# MB1134.net
KiCad netlist of a schematic drawn in Altium Designer
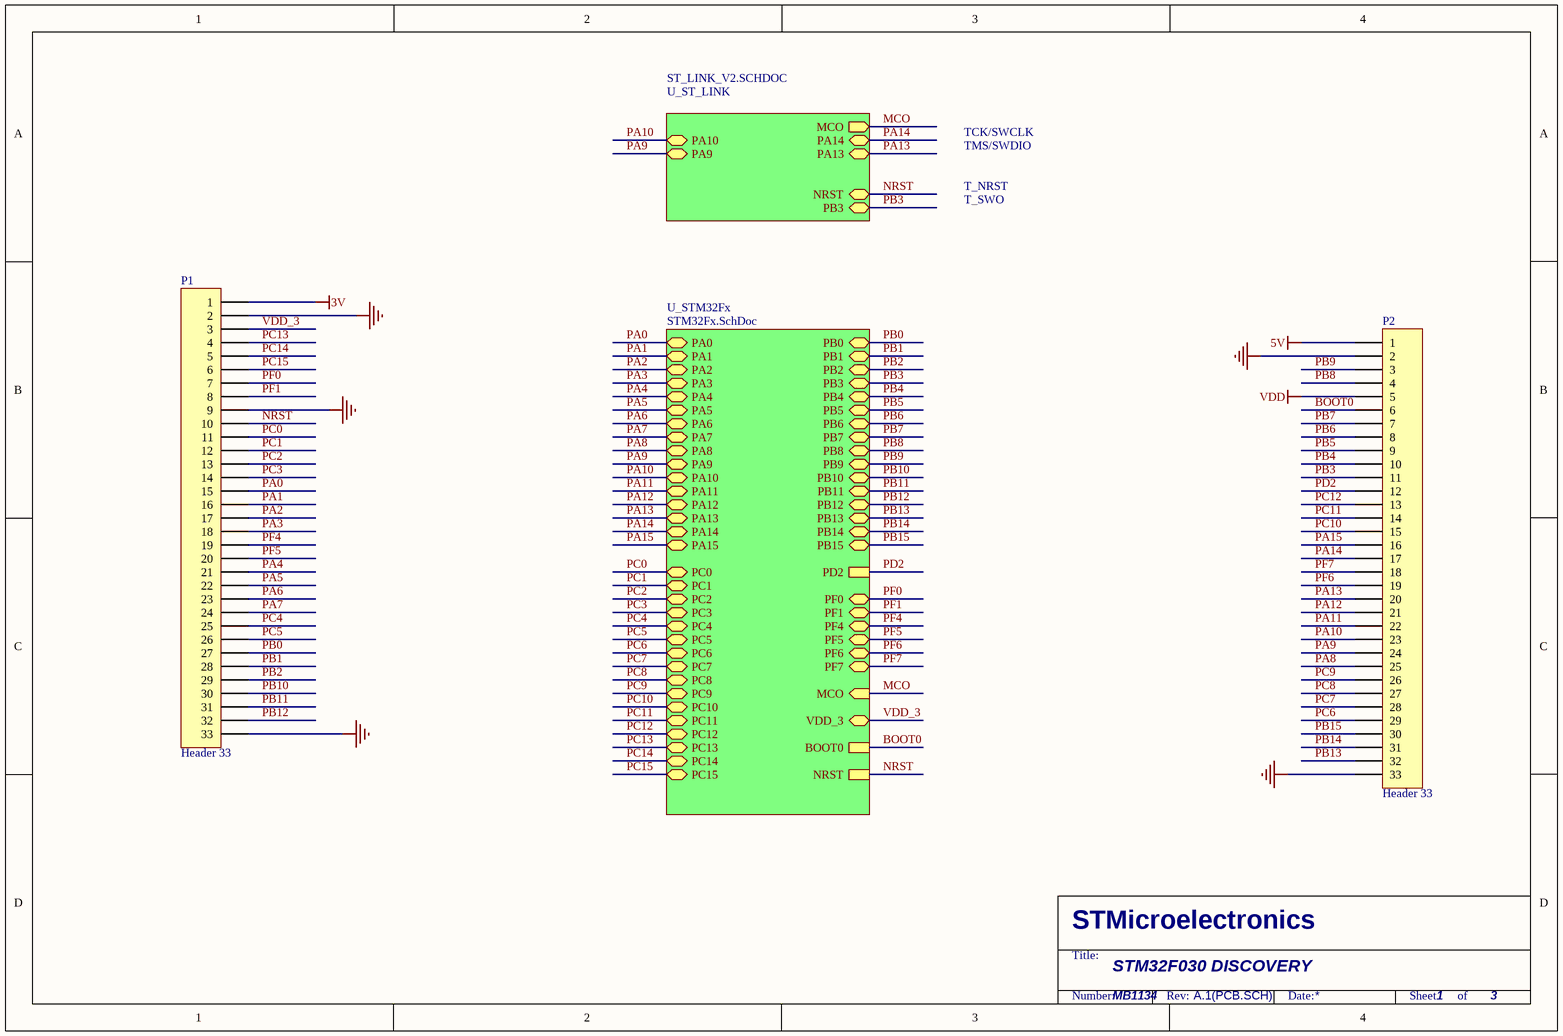
[diagram p0: MB1134.SchDoc]

(export (version "E")
  (design (tool "Eeschema 10.0.6"))
  (components
    (comp (ref "P1")
      (value "Header 33")
      (footprint "HDR1X33")
      (description "Header, 33-Pin")
      (fields (field (name "PUBLISHER") "Altium Limited"))
      (libsource (lib "") (part "Header 33_1"))
    )
    (comp (ref "P2")
      (value "Header 33")
      (footprint "HDR1X33")
      (description "Header, 33-Pin")
      (fields (field (name "PUBLISHER") "Altium Limited"))
      (libsource (lib "MB1034") (part "Header 33"))
    )
  )
  (nets
    (net (code "1") (name "/BOOT0") (class "Default")
      (node (ref "P2") (pin "6") (pinfunction "6_6") (pintype "passive"))
    )
    (net (code "3") (name "/NRST") (class "Default")
      (node (ref "P1") (pin "10") (pinfunction "10_10") (pintype "passive"))
    )
    (net (code "4") (name "/PA0") (class "Default")
      (node (ref "P1") (pin "15") (pinfunction "15_15") (pintype "passive"))
    )
    (net (code "5") (name "/PA1") (class "Default")
      (node (ref "P1") (pin "16") (pinfunction "16_16") (pintype "passive"))
    )
    (net (code "6") (name "/PA2") (class "Default")
      (node (ref "P1") (pin "17") (pinfunction "17_17") (pintype "passive"))
    )
    (net (code "7") (name "/PA3") (class "Default")
      (node (ref "P1") (pin "18") (pinfunction "18_18") (pintype "passive"))
    )
    (net (code "8") (name "/PA4") (class "Default")
      (node (ref "P1") (pin "21") (pinfunction "21_21") (pintype "passive"))
    )
    (net (code "9") (name "/PA5") (class "Default")
      (node (ref "P1") (pin "22") (pinfunction "22_22") (pintype "passive"))
    )
    (net (code "10") (name "/PA6") (class "Default")
      (node (ref "P1") (pin "23") (pinfunction "23_23") (pintype "passive"))
    )
    (net (code "11") (name "/PA7") (class "Default")
      (node (ref "P1") (pin "24") (pinfunction "24_24") (pintype "passive"))
    )
    (net (code "12") (name "/PA8") (class "Default")
      (node (ref "P2") (pin "25") (pinfunction "25_25") (pintype "passive"))
    )
    (net (code "13") (name "/PA9") (class "Default")
      (node (ref "P2") (pin "24") (pinfunction "24_24") (pintype "passive"))
    )
    (net (code "14") (name "/PA10") (class "Default")
      (node (ref "P2") (pin "23") (pinfunction "23_23") (pintype "passive"))
    )
    (net (code "15") (name "/PA11") (class "Default")
      (node (ref "P2") (pin "22") (pinfunction "22_22") (pintype "passive"))
    )
    (net (code "16") (name "/PA12") (class "Default")
      (node (ref "P2") (pin "21") (pinfunction "21_21") (pintype "passive"))
    )
    (net (code "17") (name "/PA13") (class "Default")
      (node (ref "P2") (pin "20") (pinfunction "20_20") (pintype "passive"))
    )
    (net (code "18") (name "/PA14") (class "Default")
      (node (ref "P2") (pin "17") (pinfunction "17_17") (pintype "passive"))
    )
    (net (code "19") (name "/PA15") (class "Default")
      (node (ref "P2") (pin "16") (pinfunction "16_16") (pintype "passive"))
    )
    (net (code "20") (name "/PB0") (class "Default")
      (node (ref "P1") (pin "27") (pinfunction "27_27") (pintype "passive"))
    )
    (net (code "21") (name "/PB1") (class "Default")
      (node (ref "P1") (pin "28") (pinfunction "28_28") (pintype "passive"))
    )
    (net (code "22") (name "/PB2") (class "Default")
      (node (ref "P1") (pin "29") (pinfunction "29_29") (pintype "passive"))
    )
    (net (code "23") (name "/PB3") (class "Default")
      (node (ref "P2") (pin "11") (pinfunction "11_11") (pintype "passive"))
    )
    (net (code "24") (name "/PB4") (class "Default")
      (node (ref "P2") (pin "10") (pinfunction "10_10") (pintype "passive"))
    )
    (net (code "25") (name "/PB5") (class "Default")
      (node (ref "P2") (pin "9") (pinfunction "9_9") (pintype "passive"))
    )
    (net (code "26") (name "/PB6") (class "Default")
      (node (ref "P2") (pin "8") (pinfunction "8_8") (pintype "passive"))
    )
    (net (code "27") (name "/PB7") (class "Default")
      (node (ref "P2") (pin "7") (pinfunction "7_7") (pintype "passive"))
    )
    (net (code "28") (name "/PB8") (class "Default")
      (node (ref "P2") (pin "4") (pinfunction "4_4") (pintype "passive"))
    )
    (net (code "29") (name "/PB9") (class "Default")
      (node (ref "P2") (pin "3") (pinfunction "3_3") (pintype "passive"))
    )
    (net (code "30") (name "/PB10") (class "Default")
      (node (ref "P1") (pin "30") (pinfunction "30_30") (pintype "passive"))
    )
    (net (code "31") (name "/PB11") (class "Default")
      (node (ref "P1") (pin "31") (pinfunction "31_31") (pintype "passive"))
    )
    (net (code "32") (name "/PB12") (class "Default")
      (node (ref "P1") (pin "32") (pinfunction "32_32") (pintype "passive"))
    )
    (net (code "33") (name "/PB13") (class "Default")
      (node (ref "P2") (pin "32") (pinfunction "32_32") (pintype "passive"))
    )
    (net (code "34") (name "/PB14") (class "Default")
      (node (ref "P2") (pin "31") (pinfunction "31_31") (pintype "passive"))
    )
    (net (code "35") (name "/PB15") (class "Default")
      (node (ref "P2") (pin "30") (pinfunction "30_30") (pintype "passive"))
    )
    (net (code "36") (name "/PC0") (class "Default")
      (node (ref "P1") (pin "11") (pinfunction "11_11") (pintype "passive"))
    )
    (net (code "37") (name "/PC1") (class "Default")
      (node (ref "P1") (pin "12") (pinfunction "12_12") (pintype "passive"))
    )
    (net (code "38") (name "/PC2") (class "Default")
      (node (ref "P1") (pin "13") (pinfunction "13_13") (pintype "passive"))
    )
    (net (code "39") (name "/PC3") (class "Default")
      (node (ref "P1") (pin "14") (pinfunction "14_14") (pintype "passive"))
    )
    (net (code "40") (name "/PC4") (class "Default")
      (node (ref "P1") (pin "25") (pinfunction "25_25") (pintype "passive"))
    )
    (net (code "41") (name "/PC5") (class "Default")
      (node (ref "P1") (pin "26") (pinfunction "26_26") (pintype "passive"))
    )
    (net (code "42") (name "/PC6") (class "Default")
      (node (ref "P2") (pin "29") (pinfunction "29_29") (pintype "passive"))
    )
    (net (code "43") (name "/PC7") (class "Default")
      (node (ref "P2") (pin "28") (pinfunction "28_28") (pintype "passive"))
    )
    (net (code "44") (name "/PC8") (class "Default")
      (node (ref "P2") (pin "27") (pinfunction "27_27") (pintype "passive"))
    )
    (net (code "45") (name "/PC9") (class "Default")
      (node (ref "P2") (pin "26") (pinfunction "26_26") (pintype "passive"))
    )
    (net (code "46") (name "/PC10") (class "Default")
      (node (ref "P2") (pin "15") (pinfunction "15_15") (pintype "passive"))
    )
    (net (code "47") (name "/PC11") (class "Default")
      (node (ref "P2") (pin "14") (pinfunction "14_14") (pintype "passive"))
    )
    (net (code "48") (name "/PC12") (class "Default")
      (node (ref "P2") (pin "13") (pinfunction "13_13") (pintype "passive"))
    )
    (net (code "49") (name "/PC13") (class "Default")
      (node (ref "P1") (pin "4") (pinfunction "4_4") (pintype "passive"))
    )
    (net (code "50") (name "/PC14") (class "Default")
      (node (ref "P1") (pin "5") (pinfunction "5_5") (pintype "passive"))
    )
    (net (code "51") (name "/PC15") (class "Default")
      (node (ref "P1") (pin "6") (pinfunction "6_6") (pintype "passive"))
    )
    (net (code "52") (name "/PD2") (class "Default")
      (node (ref "P2") (pin "12") (pinfunction "12_12") (pintype "passive"))
    )
    (net (code "53") (name "/PF0") (class "Default")
      (node (ref "P1") (pin "7") (pinfunction "7_7") (pintype "passive"))
    )
    (net (code "54") (name "/PF1") (class "Default")
      (node (ref "P1") (pin "8") (pinfunction "8_8") (pintype "passive"))
    )
    (net (code "55") (name "/PF4") (class "Default")
      (node (ref "P1") (pin "19") (pinfunction "19_19") (pintype "passive"))
    )
    (net (code "56") (name "/PF5") (class "Default")
      (node (ref "P1") (pin "20") (pinfunction "20_20") (pintype "passive"))
    )
    (net (code "57") (name "/PF6") (class "Default")
      (node (ref "P2") (pin "19") (pinfunction "19_19") (pintype "passive"))
    )
    (net (code "58") (name "/PF7") (class "Default")
      (node (ref "P2") (pin "18") (pinfunction "18_18") (pintype "passive"))
    )
    (net (code "59") (name "/VDD_3") (class "Default")
      (node (ref "P1") (pin "3") (pinfunction "3_3") (pintype "passive"))
    )
    (net (code "60") (name "3V") (class "Default")
      (node (ref "P1") (pin "1") (pinfunction "1_1") (pintype "passive"))
    )
    (net (code "61") (name "5V") (class "Default")
      (node (ref "P2") (pin "1") (pinfunction "1_1") (pintype "passive"))
    )
    (net (code "62") (name "GND") (class "Default")
      (node (ref "P1") (pin "2") (pinfunction "2_2") (pintype "passive"))
      (node (ref "P1") (pin "33") (pinfunction "33_33") (pintype "passive"))
      (node (ref "P1") (pin "9") (pinfunction "9_9") (pintype "passive"))
      (node (ref "P2") (pin "2") (pinfunction "2_2") (pintype "passive"))
      (node (ref "P2") (pin "33") (pinfunction "33_33") (pintype "passive"))
    )
    (net (code "63") (name "VDD") (class "Default")
      (node (ref "P2") (pin "5") (pinfunction "5_5") (pintype "passive"))
    )
  )
)
